# Sheet1.net
KiCad netlist of a schematic drawn in Altium Designer
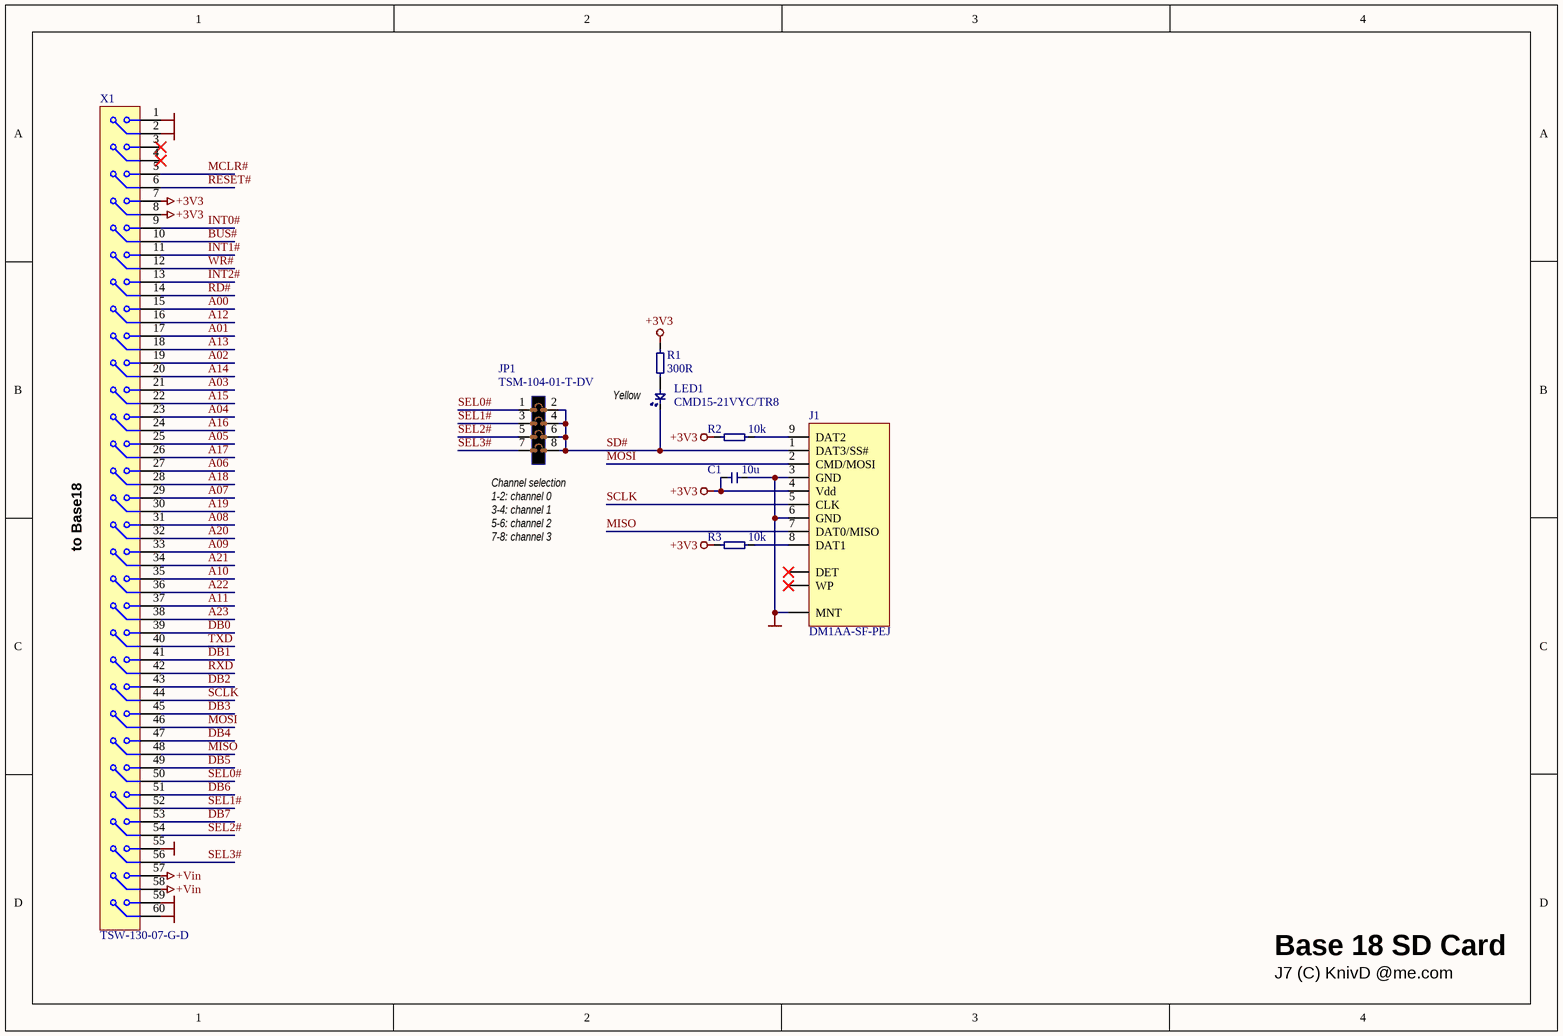
[diagram p0: Sheet1.SchDoc]

(export (version "E")
  (design (tool "Eeschema 10.0.6"))
  (components
    (comp (ref "C1")
      (value "10u")
      (footprint "CAPC3216X110N")
      (description "Capacitor")
      (libsource (lib "Discretes") (part "Capacitor"))
    )
    (comp (ref "J1")
      (value "DM1AA-SF-PEJ")
      (footprint "DM1AA-SF-PEJ")
      (description "SD card connector")
      (libsource (lib "Connectors") (part "SD (w/ card detect and WP)"))
    )
    (comp (ref "JP1")
      (value "TSM-104-01-T-DV")
      (footprint "2015-2X04XD")
      (description "2.54mm square pin header/jumper")
      (libsource (lib "Connectors") (part "Jumper 4x2"))
    )
    (comp (ref "LED1")
      (value "CMD15-21VYC/TR8")
      (footprint "LED_OSRAM_LYN971")
      (description "Light Emitting Diode")
      (libsource (lib "Discretes") (part "LED"))
    )
    (comp (ref "R1")
      (value "300R")
      (footprint "RESC3216X75N")
      (description "Resistor")
      (libsource (lib "") (part "Resistor_1"))
    )
    (comp (ref "R2")
      (value "10k")
      (footprint "RESC3216X75N")
      (description "Resistor")
      (libsource (lib "Discretes") (part "Resistor"))
    )
    (comp (ref "R3")
      (value "10k")
      (footprint "RESC3216X75N")
      (description "Resistor")
      (libsource (lib "Discretes") (part "Resistor"))
    )
    (comp (ref "X1")
      (value "TSW-130-07-G-D")
      (footprint "DIL60-M-EDGE")
      (description "Dual row, 60-way connector")
      (libsource (lib "Connectors") (part "Connector 2x30"))
    )
  )
  (nets
    (net (code "1") (name "+3V3") (class "Default")
      (node (ref "C1") (pin "1") (pintype "passive"))
      (node (ref "J1") (pin "4") (pinfunction "Vdd_4") (pintype "passive"))
      (node (ref "R1") (pin "2") (pintype "passive"))
      (node (ref "R2") (pin "2") (pintype "passive"))
      (node (ref "R3") (pin "2") (pintype "passive"))
      (node (ref "X1") (pin "7") (pinfunction "7_7") (pintype "passive"))
      (node (ref "X1") (pin "8") (pinfunction "8_8") (pintype "passive"))
    )
    (net (code "2") (name "+Vin") (class "Default")
      (node (ref "X1") (pin "57") (pinfunction "57_57") (pintype "passive"))
      (node (ref "X1") (pin "58") (pinfunction "58_58") (pintype "passive"))
    )
    (net (code "3") (name "/A00") (class "Default")
      (node (ref "X1") (pin "15") (pinfunction "15_15") (pintype "passive"))
    )
    (net (code "4") (name "/A01") (class "Default")
      (node (ref "X1") (pin "17") (pinfunction "17_17") (pintype "passive"))
    )
    (net (code "5") (name "/A02") (class "Default")
      (node (ref "X1") (pin "19") (pinfunction "19_19") (pintype "passive"))
    )
    (net (code "6") (name "/A03") (class "Default")
      (node (ref "X1") (pin "21") (pinfunction "21_21") (pintype "passive"))
    )
    (net (code "7") (name "/A04") (class "Default")
      (node (ref "X1") (pin "23") (pinfunction "23_23") (pintype "passive"))
    )
    (net (code "8") (name "/A05") (class "Default")
      (node (ref "X1") (pin "25") (pinfunction "25_25") (pintype "passive"))
    )
    (net (code "9") (name "/A06") (class "Default")
      (node (ref "X1") (pin "27") (pinfunction "27_27") (pintype "passive"))
    )
    (net (code "10") (name "/A07") (class "Default")
      (node (ref "X1") (pin "29") (pinfunction "29_29") (pintype "passive"))
    )
    (net (code "11") (name "/A08") (class "Default")
      (node (ref "X1") (pin "31") (pinfunction "31_31") (pintype "passive"))
    )
    (net (code "12") (name "/A09") (class "Default")
      (node (ref "X1") (pin "33") (pinfunction "33_33") (pintype "passive"))
    )
    (net (code "13") (name "/A10") (class "Default")
      (node (ref "X1") (pin "35") (pinfunction "35_35") (pintype "passive"))
    )
    (net (code "14") (name "/A11") (class "Default")
      (node (ref "X1") (pin "37") (pinfunction "37_37") (pintype "passive"))
    )
    (net (code "15") (name "/A12") (class "Default")
      (node (ref "X1") (pin "16") (pinfunction "16_16") (pintype "passive"))
    )
    (net (code "16") (name "/A13") (class "Default")
      (node (ref "X1") (pin "18") (pinfunction "18_18") (pintype "passive"))
    )
    (net (code "17") (name "/A14") (class "Default")
      (node (ref "X1") (pin "20") (pinfunction "20_20") (pintype "passive"))
    )
    (net (code "18") (name "/A15") (class "Default")
      (node (ref "X1") (pin "22") (pinfunction "22_22") (pintype "passive"))
    )
    (net (code "19") (name "/A16") (class "Default")
      (node (ref "X1") (pin "24") (pinfunction "24_24") (pintype "passive"))
    )
    (net (code "20") (name "/A17") (class "Default")
      (node (ref "X1") (pin "26") (pinfunction "26_26") (pintype "passive"))
    )
    (net (code "21") (name "/A18") (class "Default")
      (node (ref "X1") (pin "28") (pinfunction "28_28") (pintype "passive"))
    )
    (net (code "22") (name "/A19") (class "Default")
      (node (ref "X1") (pin "30") (pinfunction "30_30") (pintype "passive"))
    )
    (net (code "23") (name "/A20") (class "Default")
      (node (ref "X1") (pin "32") (pinfunction "32_32") (pintype "passive"))
    )
    (net (code "24") (name "/A21") (class "Default")
      (node (ref "X1") (pin "34") (pinfunction "34_34") (pintype "passive"))
    )
    (net (code "25") (name "/A22") (class "Default")
      (node (ref "X1") (pin "36") (pinfunction "36_36") (pintype "passive"))
    )
    (net (code "26") (name "/A23") (class "Default")
      (node (ref "X1") (pin "38") (pinfunction "38_38") (pintype "passive"))
    )
    (net (code "27") (name "/BUS#") (class "Default")
      (node (ref "X1") (pin "10") (pinfunction "10_10") (pintype "passive"))
    )
    (net (code "28") (name "/DB0") (class "Default")
      (node (ref "X1") (pin "39") (pinfunction "39_39") (pintype "passive"))
    )
    (net (code "29") (name "/DB1") (class "Default")
      (node (ref "X1") (pin "41") (pinfunction "41_41") (pintype "passive"))
    )
    (net (code "30") (name "/DB2") (class "Default")
      (node (ref "X1") (pin "43") (pinfunction "43_43") (pintype "passive"))
    )
    (net (code "31") (name "/DB3") (class "Default")
      (node (ref "X1") (pin "45") (pinfunction "45_45") (pintype "passive"))
    )
    (net (code "32") (name "/DB4") (class "Default")
      (node (ref "X1") (pin "47") (pinfunction "47_47") (pintype "passive"))
    )
    (net (code "33") (name "/DB5") (class "Default")
      (node (ref "X1") (pin "49") (pinfunction "49_49") (pintype "passive"))
    )
    (net (code "34") (name "/DB6") (class "Default")
      (node (ref "X1") (pin "51") (pinfunction "51_51") (pintype "passive"))
    )
    (net (code "35") (name "/DB7") (class "Default")
      (node (ref "X1") (pin "53") (pinfunction "53_53") (pintype "passive"))
    )
    (net (code "36") (name "/INT0#") (class "Default")
      (node (ref "X1") (pin "9") (pinfunction "9_9") (pintype "passive"))
    )
    (net (code "37") (name "/INT1#") (class "Default")
      (node (ref "X1") (pin "11") (pinfunction "11_11") (pintype "passive"))
    )
    (net (code "38") (name "/INT2#") (class "Default")
      (node (ref "X1") (pin "13") (pinfunction "13_13") (pintype "passive"))
    )
    (net (code "39") (name "/MCLR#") (class "Default")
      (node (ref "X1") (pin "5") (pinfunction "5_5") (pintype "passive"))
    )
    (net (code "40") (name "/MISO") (class "Default")
      (node (ref "J1") (pin "7") (pinfunction "DAT0/MISO_7") (pintype "passive"))
      (node (ref "X1") (pin "48") (pinfunction "48_48") (pintype "passive"))
    )
    (net (code "41") (name "/MOSI") (class "Default")
      (node (ref "J1") (pin "2") (pinfunction "CMD/MOSI_2") (pintype "passive"))
      (node (ref "X1") (pin "46") (pinfunction "46_46") (pintype "passive"))
    )
    (net (code "42") (name "/RD#") (class "Default")
      (node (ref "X1") (pin "14") (pinfunction "14_14") (pintype "passive"))
    )
    (net (code "43") (name "/RESET#") (class "Default")
      (node (ref "X1") (pin "6") (pinfunction "6_6") (pintype "passive"))
    )
    (net (code "44") (name "/RXD") (class "Default")
      (node (ref "X1") (pin "42") (pinfunction "42_42") (pintype "passive"))
    )
    (net (code "45") (name "/SCLK") (class "Default")
      (node (ref "J1") (pin "5") (pinfunction "CLK_5") (pintype "passive"))
      (node (ref "X1") (pin "44") (pinfunction "44_44") (pintype "passive"))
    )
    (net (code "46") (name "/SD#") (class "Default")
      (node (ref "J1") (pin "1") (pinfunction "DAT3/SS#_1") (pintype "passive"))
      (node (ref "JP1") (pin "2") (pintype "passive"))
      (node (ref "JP1") (pin "4") (pintype "passive"))
      (node (ref "JP1") (pin "6") (pintype "passive"))
      (node (ref "JP1") (pin "8") (pintype "passive"))
      (node (ref "LED1") (pin "1") (pintype "passive"))
    )
    (net (code "47") (name "/SEL0#") (class "Default")
      (node (ref "JP1") (pin "1") (pintype "passive"))
      (node (ref "X1") (pin "50") (pinfunction "50_50") (pintype "passive"))
    )
    (net (code "48") (name "/SEL1#") (class "Default")
      (node (ref "JP1") (pin "3") (pintype "passive"))
      (node (ref "X1") (pin "52") (pinfunction "52_52") (pintype "passive"))
    )
    (net (code "49") (name "/SEL2#") (class "Default")
      (node (ref "JP1") (pin "5") (pintype "passive"))
      (node (ref "X1") (pin "54") (pinfunction "54_54") (pintype "passive"))
    )
    (net (code "50") (name "/SEL3#") (class "Default")
      (node (ref "JP1") (pin "7") (pintype "passive"))
      (node (ref "X1") (pin "56") (pinfunction "56_56") (pintype "passive"))
    )
    (net (code "51") (name "/TXD") (class "Default")
      (node (ref "X1") (pin "40") (pinfunction "40_40") (pintype "passive"))
    )
    (net (code "52") (name "/WR#") (class "Default")
      (node (ref "X1") (pin "12") (pinfunction "12_12") (pintype "passive"))
    )
    (net (code "53") (name "GND") (class "Default")
      (node (ref "C1") (pin "2") (pintype "passive"))
      (node (ref "J1") (pin "0") (pinfunction "MNT_0") (pintype "passive"))
      (node (ref "J1") (pin "3") (pinfunction "GND_3") (pintype "passive"))
      (node (ref "J1") (pin "6") (pinfunction "GND_6") (pintype "passive"))
      (node (ref "X1") (pin "1") (pinfunction "1_1") (pintype "passive"))
      (node (ref "X1") (pin "2") (pinfunction "2_2") (pintype "passive"))
      (node (ref "X1") (pin "55") (pinfunction "55_55") (pintype "passive"))
      (node (ref "X1") (pin "59") (pinfunction "59_59") (pintype "passive"))
      (node (ref "X1") (pin "60") (pinfunction "60_60") (pintype "passive"))
    )
    (net (code "54") (name "Net-(J1-DAT1)") (class "Default")
      (node (ref "J1") (pin "8") (pinfunction "DAT1_8") (pintype "passive"))
      (node (ref "R3") (pin "1") (pintype "passive"))
    )
    (net (code "55") (name "Net-(J1-DAT2)") (class "Default")
      (node (ref "J1") (pin "9") (pinfunction "DAT2_9") (pintype "passive"))
      (node (ref "R2") (pin "1") (pintype "passive"))
    )
    (net (code "56") (name "Net-(LED1-Pad2)") (class "Default")
      (node (ref "LED1") (pin "2") (pintype "passive"))
      (node (ref "R1") (pin "1") (pintype "passive"))
    )
    (net (code "57") (name "unconnected-(J1-PadDET)") (class "Default")
      (node (ref "J1") (pin "DET") (pinfunction "DET_DET") (pintype "passive+no_connect"))
    )
    (net (code "58") (name "unconnected-(J1-PadWP)") (class "Default")
      (node (ref "J1") (pin "WP") (pinfunction "WP_WP") (pintype "passive+no_connect"))
    )
    (net (code "59") (name "unconnected-(X1-Pad3)") (class "Default")
      (node (ref "X1") (pin "3") (pinfunction "3_3") (pintype "passive+no_connect"))
    )
    (net (code "60") (name "unconnected-(X1-Pad4)") (class "Default")
      (node (ref "X1") (pin "4") (pinfunction "4_4") (pintype "passive+no_connect"))
    )
  )
)
